# LED_Driver_-_3.net
KiCad netlist of a schematic drawn in Altium Designer
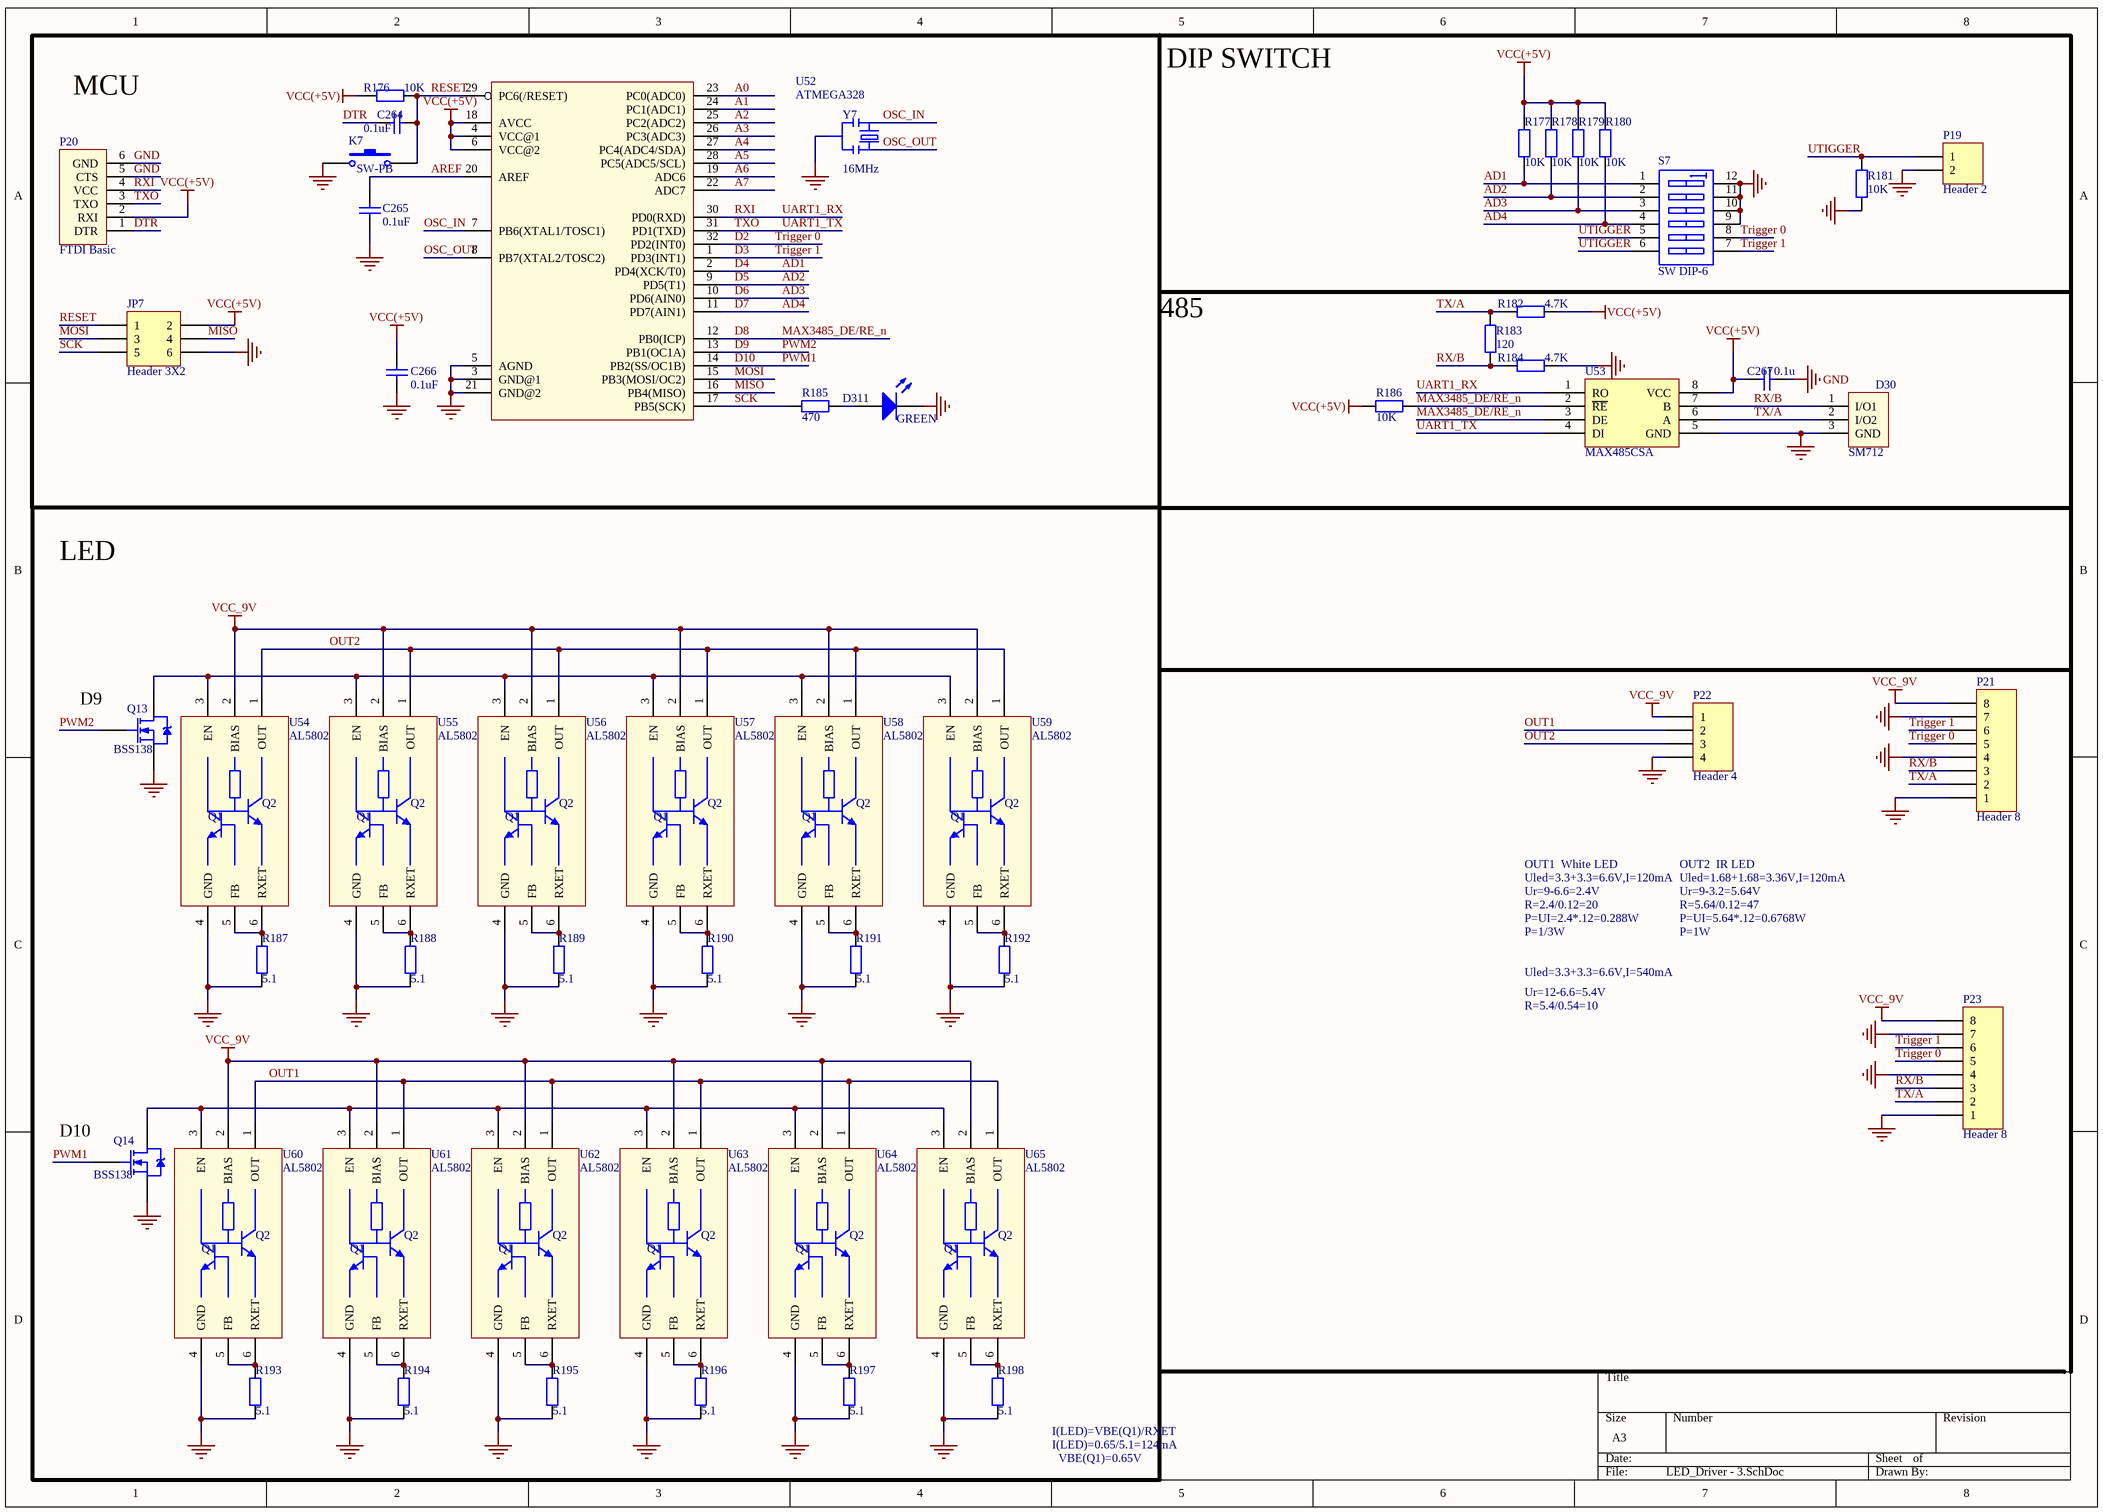
[diagram p0: LED_Driver - 3.SchDoc]

(export (version "E")
  (design (tool "Eeschema 10.0.6"))
  (components
    (comp (ref "C264")
      (value "0.1uF")
      (footprint "C0603")
      (description "Capacitor")
      (fields (field (name "IPARTNUMBER") "C100nF25V10%X7R") (field (name "VOLTAGE") "25V"))
      (libsource (lib "Schlib1") (part "CAP SMT C100nF25V10%X7R"))
    )
    (comp (ref "C265")
      (value "0.1uF")
      (footprint "C0603")
      (description "Capacitor")
      (fields (field (name "IPARTNUMBER") "C100nF25V10%X7R") (field (name "VOLTAGE") "25V"))
      (libsource (lib "Schlib1") (part "CAP SMT C100nF25V10%X7R"))
    )
    (comp (ref "C266")
      (value "0.1uF")
      (footprint "C0603")
      (description "Capacitor")
      (fields (field (name "IPARTNUMBER") "C100nF25V10%X7R") (field (name "VOLTAGE") "25V"))
      (libsource (lib "Schlib1") (part "CAP SMT C100nF25V10%X7R"))
    )
    (comp (ref "C267")
      (value "0.1u")
      (footprint "C0603")
      (description "Capacitor")
      (fields (field (name "PUBLISHER") "Altium Limited"))
      (libsource (lib "Miscellaneous Devices") (part "Cap"))
    )
    (comp (ref "D30")
      (value "SM712")
      (footprint "SOT23-3")
      (libsource (lib "STM32F4_CAM V2.0") (part "SM712"))
    )
    (comp (ref "D31")
      (value "GREEN")
      (footprint "LED0805")
      (description "Typical INFRARED GaAs LED")
      (fields (field (name "PUBLISHER") "Altium Limited"))
      (libsource (lib "DM642") (part "LED0"))
    )
    (comp (ref "JP7")
      (value "Header 3X2")
      (footprint "MHDR1X6")
      (description "Header, 3-Pin, Dual row")
      (fields (field (name "PUBLISHER") "Altium Limited"))
      (libsource (lib "Miscellaneous Connectors") (part "Header 3X2"))
    )
    (comp (ref "K7")
      (value "SW-PB")
      (footprint "157SW")
      (description "Switch")
      (fields (field (name "PUBLISHER") "Altium Limited"))
      (libsource (lib "Miscellaneous Devices") (part "SW-PB"))
    )
    (comp (ref "P19")
      (value "Header 2")
      (footprint "HDR1X2")
      (description "Header, 2-Pin")
      (fields (field (name "PUBLISHER") "Altium Limited"))
      (libsource (lib "Miscellaneous Connectors") (part "Header 2"))
    )
    (comp (ref "P20")
      (value "FTDI Basic")
      (footprint "MHDR1X6")
      (libsource (lib "PCB_Project1") (part "ARDUINO_SERIAL_PROGRAMPTH"))
    )
    (comp (ref "P21")
      (value "Header 8")
      (footprint "SH_1.25MM*8")
      (description "Header, 8-Pin")
      (fields (field (name "PUBLISHER") "Altium Limited"))
      (libsource (lib "Miscellaneous Connectors") (part "Header 8"))
    )
    (comp (ref "P22")
      (value "Header 4")
      (footprint "SMT_1.25MM*4")
      (description "Header, 4-Pin")
      (fields (field (name "PUBLISHER") "Altium Limited"))
      (libsource (lib "Miscellaneous Connectors") (part "Header 4"))
    )
    (comp (ref "P23")
      (value "Header 8")
      (footprint "SH_1.25MM*8")
      (description "Header, 8-Pin")
      (fields (field (name "PUBLISHER") "Altium Limited"))
      (libsource (lib "Miscellaneous Connectors") (part "Header 8"))
    )
    (comp (ref "Q13")
      (value "BSS138")
      (footprint "SOT-23 (Standard)")
      (fields
        (field (name "MANUFACTURER") "Fairchild Semiconductor")
        (field (name "MANUFACTURER PART NUMBER") "BSS123")
      )
      (libsource (lib "Miscellaneous_Devices") (part "NMOS"))
    )
    (comp (ref "Q14")
      (value "BSS138")
      (footprint "SOT-23 (Standard)")
      (fields
        (field (name "MANUFACTURER") "Fairchild Semiconductor")
        (field (name "MANUFACTURER PART NUMBER") "BSS123")
      )
      (libsource (lib "Miscellaneous_Devices") (part "NMOS"))
    )
    (comp (ref "R176")
      (value "10K")
      (footprint "R0603")
      (description "Resistor")
      (libsource (lib "") (part "Res2_1"))
    )
    (comp (ref "R177")
      (value "10K")
      (footprint "R0603")
      (description "Resistor")
      (libsource (lib "DM642") (part "Res2"))
    )
    (comp (ref "R178")
      (value "10K")
      (footprint "R0603")
      (description "Resistor")
      (libsource (lib "DM642") (part "Res2"))
    )
    (comp (ref "R179")
      (value "10K")
      (footprint "R0603")
      (description "Resistor")
      (libsource (lib "DM642") (part "Res2"))
    )
    (comp (ref "R180")
      (value "10K")
      (footprint "R0603")
      (description "Resistor")
      (libsource (lib "DM642") (part "Res2"))
    )
    (comp (ref "R181")
      (value "10K")
      (footprint "R0603")
      (description "Resistor")
      (fields (field (name "PUBLISHER") "Altium Limited"))
      (libsource (lib "Miscellaneous Devices") (part "Res2"))
    )
    (comp (ref "R182")
      (value "4.7K")
      (footprint "R0603")
      (description "Resistor")
      (libsource (lib "") (part "Res2_2"))
    )
    (comp (ref "R183")
      (value "120")
      (footprint "R0603")
      (description "Resistor")
      (libsource (lib "DM642") (part "Res2"))
    )
    (comp (ref "R184")
      (value "4.7K")
      (footprint "R0603")
      (description "Resistor")
      (libsource (lib "") (part "Res2_2"))
    )
    (comp (ref "R185")
      (value "470")
      (footprint "R0603")
      (description "Resistor")
      (libsource (lib "") (part "Res2_1"))
    )
    (comp (ref "R186")
      (value "10K")
      (footprint "R0603")
      (description "Resistor")
      (libsource (lib "") (part "Res2_2"))
    )
    (comp (ref "R187")
      (value "5.1")
      (footprint "R0603")
      (description "Resistor")
      (libsource (lib "DM642") (part "Res2"))
    )
    (comp (ref "R188")
      (value "5.1")
      (footprint "R0603")
      (description "Resistor")
      (libsource (lib "DM642") (part "Res2"))
    )
    (comp (ref "R189")
      (value "5.1")
      (footprint "R0603")
      (description "Resistor")
      (libsource (lib "DM642") (part "Res2"))
    )
    (comp (ref "R190")
      (value "5.1")
      (footprint "R0603")
      (description "Resistor")
      (libsource (lib "DM642") (part "Res2"))
    )
    (comp (ref "R191")
      (value "5.1")
      (footprint "R0603")
      (description "Resistor")
      (libsource (lib "DM642") (part "Res2"))
    )
    (comp (ref "R192")
      (value "5.1")
      (footprint "R0603")
      (description "Resistor")
      (libsource (lib "DM642") (part "Res2"))
    )
    (comp (ref "R193")
      (value "5.1")
      (footprint "R0603")
      (description "Resistor")
      (libsource (lib "DM642") (part "Res2"))
    )
    (comp (ref "R194")
      (value "5.1")
      (footprint "R0603")
      (description "Resistor")
      (libsource (lib "DM642") (part "Res2"))
    )
    (comp (ref "R195")
      (value "5.1")
      (footprint "R0603")
      (description "Resistor")
      (libsource (lib "DM642") (part "Res2"))
    )
    (comp (ref "R196")
      (value "5.1")
      (footprint "R0603")
      (description "Resistor")
      (libsource (lib "DM642") (part "Res2"))
    )
    (comp (ref "R197")
      (value "5.1")
      (footprint "R0603")
      (description "Resistor")
      (libsource (lib "DM642") (part "Res2"))
    )
    (comp (ref "R198")
      (value "5.1")
      (footprint "R0603")
      (description "Resistor")
      (libsource (lib "DM642") (part "Res2"))
    )
    (comp (ref "S7")
      (value "SW DIP-6")
      (footprint "DIP_SW_6WAY_SMD")
      (description "DIP Switch, 6 Position, SPST")
      (fields (field (name "PUBLISHER") "Altium Limited"))
      (libsource (lib "Miscellaneous Devices") (part "SW DIP-6"))
    )
    (comp (ref "U52")
      (value "ATMEGA328")
      (footprint "TQFP32-08")
      (libsource (lib "PCB_Project1") (part "ATMEGA168"))
    )
    (comp (ref "U53")
      (value "MAX485CSA")
      (footprint "SOIC-8")
      (libsource (lib "STM32F4_CAM V1.2") (part "MAX3485CSA"))
    )
    (comp (ref "U54") (value "AL5802") (footprint "SOT26") (libsource (lib "LED") (part "AL5802")))
    (comp (ref "U55") (value "AL5802") (footprint "SOT26") (libsource (lib "LED") (part "AL5802")))
    (comp (ref "U56") (value "AL5802") (footprint "SOT26") (libsource (lib "LED") (part "AL5802")))
    (comp (ref "U57") (value "AL5802") (footprint "SOT26") (libsource (lib "LED") (part "AL5802")))
    (comp (ref "U58") (value "AL5802") (footprint "SOT26") (libsource (lib "LED") (part "AL5802")))
    (comp (ref "U59") (value "AL5802") (footprint "SOT26") (libsource (lib "LED") (part "AL5802")))
    (comp (ref "U60") (value "AL5802") (footprint "SOT26") (libsource (lib "LED") (part "AL5802")))
    (comp (ref "U61") (value "AL5802") (footprint "SOT26") (libsource (lib "LED") (part "AL5802")))
    (comp (ref "U62") (value "AL5802") (footprint "SOT26") (libsource (lib "LED") (part "AL5802")))
    (comp (ref "U63") (value "AL5802") (footprint "SOT26") (libsource (lib "LED") (part "AL5802")))
    (comp (ref "U64") (value "AL5802") (footprint "SOT26") (libsource (lib "LED") (part "AL5802")))
    (comp (ref "U65") (value "AL5802") (footprint "SOT26") (libsource (lib "LED") (part "AL5802")))
    (comp (ref "Y7")
      (value "16MHz")
      (footprint "RESONATOR-SMD")
      (libsource (lib "SparkFun") (part "RESONATORSMD"))
    )
  )
  (nets
    (net (code "1") (name "/A0") (class "Default")
      (node (ref "U52") (pin "23") (pinfunction "PC0(ADC0)_23") (pintype "passive"))
    )
    (net (code "2") (name "/A1") (class "Default")
      (node (ref "U52") (pin "24") (pinfunction "PC1(ADC1)_24") (pintype "passive"))
    )
    (net (code "3") (name "/A2") (class "Default")
      (node (ref "U52") (pin "25") (pinfunction "PC2(ADC2)_25") (pintype "passive"))
    )
    (net (code "4") (name "/A3") (class "Default")
      (node (ref "U52") (pin "26") (pinfunction "PC3(ADC3)_26") (pintype "passive"))
    )
    (net (code "5") (name "/A4") (class "Default")
      (node (ref "U52") (pin "27") (pinfunction "PC4(ADC4/SDA)_27") (pintype "passive"))
    )
    (net (code "6") (name "/A5") (class "Default")
      (node (ref "U52") (pin "28") (pinfunction "PC5(ADC5/SCL)_28") (pintype "passive"))
    )
    (net (code "7") (name "/A6") (class "Default")
      (node (ref "U52") (pin "19") (pinfunction "ADC6_19") (pintype "passive"))
    )
    (net (code "8") (name "/A7") (class "Default")
      (node (ref "U52") (pin "22") (pinfunction "ADC7_22") (pintype "passive"))
    )
    (net (code "9") (name "/AD1") (class "Default")
      (node (ref "R177") (pin "2") (pinfunction "2_2") (pintype "passive"))
      (node (ref "S7") (pin "1") (pinfunction "A1_1") (pintype "passive"))
      (node (ref "U52") (pin "2") (pinfunction "PD4(XCK/T0)_2") (pintype "passive"))
    )
    (net (code "10") (name "/AD2") (class "Default")
      (node (ref "R178") (pin "2") (pinfunction "2_2") (pintype "passive"))
      (node (ref "S7") (pin "2") (pinfunction "A2_2") (pintype "passive"))
      (node (ref "U52") (pin "9") (pinfunction "PD5(T1)_9") (pintype "passive"))
    )
    (net (code "11") (name "/AD3") (class "Default")
      (node (ref "R179") (pin "2") (pinfunction "2_2") (pintype "passive"))
      (node (ref "S7") (pin "3") (pinfunction "A3_3") (pintype "passive"))
      (node (ref "U52") (pin "10") (pinfunction "PD6(AIN0)_10") (pintype "passive"))
    )
    (net (code "12") (name "/AD4") (class "Default")
      (node (ref "R180") (pin "2") (pinfunction "2_2") (pintype "passive"))
      (node (ref "S7") (pin "4") (pinfunction "A4_4") (pintype "passive"))
      (node (ref "U52") (pin "11") (pinfunction "PD7(AIN1)_11") (pintype "passive"))
    )
    (net (code "13") (name "/AREF") (class "Default")
      (node (ref "C265") (pin "2") (pinfunction "2_2") (pintype "passive"))
      (node (ref "U52") (pin "20") (pinfunction "AREF_20") (pintype "passive"))
    )
    (net (code "14") (name "/D2") (class "Default")
      (node (ref "P21") (pin "5") (pinfunction "5_5") (pintype "passive"))
      (node (ref "P23") (pin "5") (pinfunction "5_5") (pintype "passive"))
      (node (ref "S7") (pin "8") (pinfunction "B5_8") (pintype "passive"))
      (node (ref "U52") (pin "32") (pinfunction "PD2(INT0)_32") (pintype "passive"))
    )
    (net (code "15") (name "/D3") (class "Default")
      (node (ref "P21") (pin "6") (pinfunction "6_6") (pintype "passive"))
      (node (ref "P23") (pin "6") (pinfunction "6_6") (pintype "passive"))
      (node (ref "S7") (pin "7") (pinfunction "B6_7") (pintype "passive"))
      (node (ref "U52") (pin "1") (pinfunction "PD3(INT1)_1") (pintype "passive"))
    )
    (net (code "16") (name "/D8") (class "Default")
      (node (ref "R186") (pin "1") (pinfunction "1_1") (pintype "passive"))
      (node (ref "U52") (pin "12") (pinfunction "PB0(ICP)_12") (pintype "passive"))
      (node (ref "U53") (pin "2") (pinfunction "~{RE}_2") (pintype "passive"))
      (node (ref "U53") (pin "3") (pinfunction "DE_3") (pintype "passive"))
    )
    (net (code "17") (name "/D9") (class "Default")
      (node (ref "Q13") (pin "G") (pinfunction "G_G") (pintype "passive"))
      (node (ref "U52") (pin "13") (pinfunction "PB1(OC1A)_13") (pintype "passive"))
    )
    (net (code "18") (name "/D10") (class "Default")
      (node (ref "Q14") (pin "G") (pinfunction "G_G") (pintype "passive"))
      (node (ref "U52") (pin "14") (pinfunction "PB2(SS/OC1B)_14") (pintype "passive"))
    )
    (net (code "19") (name "/DTR") (class "Default")
      (node (ref "C264") (pin "1") (pinfunction "1_1") (pintype "passive"))
      (node (ref "P20") (pin "1") (pinfunction "DTR_1") (pintype "passive"))
    )
    (net (code "20") (name "/MISO") (class "Default")
      (node (ref "JP7") (pin "4") (pinfunction "4_4") (pintype "passive"))
      (node (ref "U52") (pin "16") (pinfunction "PB4(MISO)_16") (pintype "passive"))
    )
    (net (code "21") (name "/MOSI") (class "Default")
      (node (ref "JP7") (pin "3") (pinfunction "3_3") (pintype "passive"))
      (node (ref "U52") (pin "15") (pinfunction "PB3(MOSI/OC2)_15") (pintype "passive"))
    )
    (net (code "22") (name "/OSC_IN") (class "Default")
      (node (ref "U52") (pin "7") (pinfunction "PB6(XTAL1/TOSC1)_7") (pintype "passive"))
      (node (ref "Y7") (pin "3") (pinfunction "3_3") (pintype "passive"))
    )
    (net (code "23") (name "/OSC_OUT") (class "Default")
      (node (ref "U52") (pin "8") (pinfunction "PB7(XTAL2/TOSC2)_8") (pintype "passive"))
      (node (ref "Y7") (pin "1") (pinfunction "1_1") (pintype "passive"))
    )
    (net (code "24") (name "/OUT1") (class "Default")
      (node (ref "P22") (pin "2") (pinfunction "2_2") (pintype "passive"))
      (node (ref "U60") (pin "1") (pinfunction "OUT_1") (pintype "passive"))
      (node (ref "U61") (pin "1") (pinfunction "OUT_1") (pintype "passive"))
      (node (ref "U62") (pin "1") (pinfunction "OUT_1") (pintype "passive"))
      (node (ref "U63") (pin "1") (pinfunction "OUT_1") (pintype "passive"))
      (node (ref "U64") (pin "1") (pinfunction "OUT_1") (pintype "passive"))
      (node (ref "U65") (pin "1") (pinfunction "OUT_1") (pintype "passive"))
    )
    (net (code "25") (name "/OUT2") (class "Default")
      (node (ref "P22") (pin "3") (pinfunction "3_3") (pintype "passive"))
      (node (ref "U54") (pin "1") (pinfunction "OUT_1") (pintype "passive"))
      (node (ref "U55") (pin "1") (pinfunction "OUT_1") (pintype "passive"))
      (node (ref "U56") (pin "1") (pinfunction "OUT_1") (pintype "passive"))
      (node (ref "U57") (pin "1") (pinfunction "OUT_1") (pintype "passive"))
      (node (ref "U58") (pin "1") (pinfunction "OUT_1") (pintype "passive"))
      (node (ref "U59") (pin "1") (pinfunction "OUT_1") (pintype "passive"))
    )
    (net (code "26") (name "/RESET") (class "Default")
      (node (ref "C264") (pin "2") (pinfunction "2_2") (pintype "passive"))
      (node (ref "JP7") (pin "1") (pinfunction "1_1") (pintype "passive"))
      (node (ref "K7") (pin "2") (pinfunction "2_2") (pintype "passive"))
      (node (ref "R176") (pin "2") (pinfunction "2_2") (pintype "passive"))
      (node (ref "U52") (pin "29") (pinfunction "PC6(/RESET)_29") (pintype "passive"))
    )
    (net (code "27") (name "/RXI") (class "Default")
      (node (ref "P20") (pin "4") (pinfunction "VCC_4") (pintype "passive"))
      (node (ref "U52") (pin "30") (pinfunction "PD0(RXD)_30") (pintype "passive"))
      (node (ref "U53") (pin "1") (pinfunction "RO_1") (pintype "passive"))
    )
    (net (code "28") (name "/RX{slash}B") (class "Default")
      (node (ref "D30") (pin "1") (pinfunction "I/O1_1") (pintype "passive"))
      (node (ref "P21") (pin "3") (pinfunction "3_3") (pintype "passive"))
      (node (ref "P23") (pin "3") (pinfunction "3_3") (pintype "passive"))
      (node (ref "R183") (pin "2") (pinfunction "2_2") (pintype "passive"))
      (node (ref "R184") (pin "2") (pinfunction "2_2") (pintype "passive"))
      (node (ref "U53") (pin "7") (pinfunction "B_7") (pintype "passive"))
    )
    (net (code "29") (name "/SCK") (class "Default")
      (node (ref "JP7") (pin "5") (pinfunction "5_5") (pintype "passive"))
      (node (ref "R185") (pin "1") (pinfunction "1_1") (pintype "passive"))
      (node (ref "U52") (pin "17") (pinfunction "PB5(SCK)_17") (pintype "passive"))
    )
    (net (code "30") (name "/TXO") (class "Default")
      (node (ref "P20") (pin "3") (pinfunction "TXO_3") (pintype "passive"))
      (node (ref "U52") (pin "31") (pinfunction "PD1(TXD)_31") (pintype "passive"))
      (node (ref "U53") (pin "4") (pinfunction "DI_4") (pintype "passive"))
    )
    (net (code "31") (name "/TX{slash}A") (class "Default")
      (node (ref "D30") (pin "2") (pinfunction "I/O2_2") (pintype "passive"))
      (node (ref "P21") (pin "2") (pinfunction "2_2") (pintype "passive"))
      (node (ref "P23") (pin "2") (pinfunction "2_2") (pintype "passive"))
      (node (ref "R182") (pin "2") (pinfunction "2_2") (pintype "passive"))
      (node (ref "R183") (pin "1") (pinfunction "1_1") (pintype "passive"))
      (node (ref "U53") (pin "6") (pinfunction "A_6") (pintype "passive"))
    )
    (net (code "32") (name "/UTIGGER") (class "Default")
      (node (ref "P19") (pin "1") (pinfunction "1_1") (pintype "passive"))
      (node (ref "R181") (pin "2") (pinfunction "2_2") (pintype "passive"))
      (node (ref "S7") (pin "5") (pinfunction "A5_5") (pintype "passive"))
      (node (ref "S7") (pin "6") (pinfunction "A6_6") (pintype "passive"))
    )
    (net (code "33") (name "GND") (class "Default")
      (node (ref "C265") (pin "1") (pinfunction "1_1") (pintype "passive"))
      (node (ref "C266") (pin "2") (pinfunction "2_2") (pintype "passive"))
      (node (ref "C267") (pin "1") (pinfunction "1_1") (pintype "passive"))
      (node (ref "D30") (pin "3") (pinfunction "GND_3") (pintype "passive"))
      (node (ref "D31") (pin "2") (pinfunction "K_2") (pintype "passive"))
      (node (ref "JP7") (pin "6") (pinfunction "6_6") (pintype "passive"))
      (node (ref "K7") (pin "1") (pinfunction "1_1") (pintype "passive"))
      (node (ref "P19") (pin "2") (pinfunction "2_2") (pintype "passive"))
      (node (ref "P20") (pin "5") (pinfunction "CTS_5") (pintype "passive"))
      (node (ref "P20") (pin "6") (pinfunction "GND_6") (pintype "passive"))
      (node (ref "P21") (pin "1") (pinfunction "1_1") (pintype "passive"))
      (node (ref "P21") (pin "4") (pinfunction "4_4") (pintype "passive"))
      (node (ref "P21") (pin "7") (pinfunction "7_7") (pintype "passive"))
      (node (ref "P22") (pin "4") (pinfunction "4_4") (pintype "passive"))
      (node (ref "P23") (pin "1") (pinfunction "1_1") (pintype "passive"))
      (node (ref "P23") (pin "4") (pinfunction "4_4") (pintype "passive"))
      (node (ref "P23") (pin "7") (pinfunction "7_7") (pintype "passive"))
      (node (ref "Q13") (pin "S") (pinfunction "S_S") (pintype "passive"))
      (node (ref "Q14") (pin "S") (pinfunction "S_S") (pintype "passive"))
      (node (ref "R181") (pin "1") (pinfunction "1_1") (pintype "passive"))
      (node (ref "R184") (pin "1") (pinfunction "1_1") (pintype "passive"))
      (node (ref "R187") (pin "2") (pinfunction "2_2") (pintype "passive"))
      (node (ref "R188") (pin "2") (pinfunction "2_2") (pintype "passive"))
      (node (ref "R189") (pin "2") (pinfunction "2_2") (pintype "passive"))
      (node (ref "R190") (pin "2") (pinfunction "2_2") (pintype "passive"))
      (node (ref "R191") (pin "2") (pinfunction "2_2") (pintype "passive"))
      (node (ref "R192") (pin "2") (pinfunction "2_2") (pintype "passive"))
      (node (ref "R193") (pin "2") (pinfunction "2_2") (pintype "passive"))
      (node (ref "R194") (pin "2") (pinfunction "2_2") (pintype "passive"))
      (node (ref "R195") (pin "2") (pinfunction "2_2") (pintype "passive"))
      (node (ref "R196") (pin "2") (pinfunction "2_2") (pintype "passive"))
      (node (ref "R197") (pin "2") (pinfunction "2_2") (pintype "passive"))
      (node (ref "R198") (pin "2") (pinfunction "2_2") (pintype "passive"))
      (node (ref "S7") (pin "10") (pinfunction "B3_10") (pintype "passive"))
      (node (ref "S7") (pin "11") (pinfunction "B2_11") (pintype "passive"))
      (node (ref "S7") (pin "12") (pinfunction "B1_12") (pintype "passive"))
      (node (ref "S7") (pin "9") (pinfunction "B4_9") (pintype "passive"))
      (node (ref "U52") (pin "21") (pinfunction "GND@2_21") (pintype "passive"))
      (node (ref "U52") (pin "3") (pinfunction "GND@1_3") (pintype "passive"))
      (node (ref "U52") (pin "5") (pinfunction "AGND_5") (pintype "passive"))
      (node (ref "U53") (pin "5") (pinfunction "GND_5") (pintype "passive"))
      (node (ref "U54") (pin "4") (pinfunction "GND_4") (pintype "passive"))
      (node (ref "U55") (pin "4") (pinfunction "GND_4") (pintype "passive"))
      (node (ref "U56") (pin "4") (pinfunction "GND_4") (pintype "passive"))
      (node (ref "U57") (pin "4") (pinfunction "GND_4") (pintype "passive"))
      (node (ref "U58") (pin "4") (pinfunction "GND_4") (pintype "passive"))
      (node (ref "U59") (pin "4") (pinfunction "GND_4") (pintype "passive"))
      (node (ref "U60") (pin "4") (pinfunction "GND_4") (pintype "passive"))
      (node (ref "U61") (pin "4") (pinfunction "GND_4") (pintype "passive"))
      (node (ref "U62") (pin "4") (pinfunction "GND_4") (pintype "passive"))
      (node (ref "U63") (pin "4") (pinfunction "GND_4") (pintype "passive"))
      (node (ref "U64") (pin "4") (pinfunction "GND_4") (pintype "passive"))
      (node (ref "U65") (pin "4") (pinfunction "GND_4") (pintype "passive"))
      (node (ref "Y7") (pin "2") (pinfunction "2_2") (pintype "passive"))
    )
    (net (code "34") (name "Net-(D31-A)") (class "Default")
      (node (ref "D31") (pin "1") (pinfunction "A_1") (pintype "passive"))
      (node (ref "R185") (pin "2") (pinfunction "2_2") (pintype "passive"))
    )
    (net (code "35") (name "Net-(U54-EN)") (class "Default")
      (node (ref "Q13") (pin "D") (pinfunction "D_D") (pintype "passive"))
      (node (ref "U54") (pin "3") (pinfunction "EN_3") (pintype "passive"))
      (node (ref "U55") (pin "3") (pinfunction "EN_3") (pintype "passive"))
      (node (ref "U56") (pin "3") (pinfunction "EN_3") (pintype "passive"))
      (node (ref "U57") (pin "3") (pinfunction "EN_3") (pintype "passive"))
      (node (ref "U58") (pin "3") (pinfunction "EN_3") (pintype "passive"))
      (node (ref "U59") (pin "3") (pinfunction "EN_3") (pintype "passive"))
    )
    (net (code "36") (name "Net-(U54-FB)") (class "Default")
      (node (ref "R187") (pin "1") (pinfunction "1_1") (pintype "passive"))
      (node (ref "U54") (pin "5") (pinfunction "FB_5") (pintype "passive"))
      (node (ref "U54") (pin "6") (pinfunction "RXET_6") (pintype "passive"))
    )
    (net (code "37") (name "Net-(U55-FB)") (class "Default")
      (node (ref "R188") (pin "1") (pinfunction "1_1") (pintype "passive"))
      (node (ref "U55") (pin "5") (pinfunction "FB_5") (pintype "passive"))
      (node (ref "U55") (pin "6") (pinfunction "RXET_6") (pintype "passive"))
    )
    (net (code "38") (name "Net-(U56-FB)") (class "Default")
      (node (ref "R189") (pin "1") (pinfunction "1_1") (pintype "passive"))
      (node (ref "U56") (pin "5") (pinfunction "FB_5") (pintype "passive"))
      (node (ref "U56") (pin "6") (pinfunction "RXET_6") (pintype "passive"))
    )
    (net (code "39") (name "Net-(U57-FB)") (class "Default")
      (node (ref "R190") (pin "1") (pinfunction "1_1") (pintype "passive"))
      (node (ref "U57") (pin "5") (pinfunction "FB_5") (pintype "passive"))
      (node (ref "U57") (pin "6") (pinfunction "RXET_6") (pintype "passive"))
    )
    (net (code "40") (name "Net-(U58-FB)") (class "Default")
      (node (ref "R191") (pin "1") (pinfunction "1_1") (pintype "passive"))
      (node (ref "U58") (pin "5") (pinfunction "FB_5") (pintype "passive"))
      (node (ref "U58") (pin "6") (pinfunction "RXET_6") (pintype "passive"))
    )
    (net (code "41") (name "Net-(U59-FB)") (class "Default")
      (node (ref "R192") (pin "1") (pinfunction "1_1") (pintype "passive"))
      (node (ref "U59") (pin "5") (pinfunction "FB_5") (pintype "passive"))
      (node (ref "U59") (pin "6") (pinfunction "RXET_6") (pintype "passive"))
    )
    (net (code "42") (name "Net-(U60-EN)") (class "Default")
      (node (ref "Q14") (pin "D") (pinfunction "D_D") (pintype "passive"))
      (node (ref "U60") (pin "3") (pinfunction "EN_3") (pintype "passive"))
      (node (ref "U61") (pin "3") (pinfunction "EN_3") (pintype "passive"))
      (node (ref "U62") (pin "3") (pinfunction "EN_3") (pintype "passive"))
      (node (ref "U63") (pin "3") (pinfunction "EN_3") (pintype "passive"))
      (node (ref "U64") (pin "3") (pinfunction "EN_3") (pintype "passive"))
      (node (ref "U65") (pin "3") (pinfunction "EN_3") (pintype "passive"))
    )
    (net (code "43") (name "Net-(U60-FB)") (class "Default")
      (node (ref "R193") (pin "1") (pinfunction "1_1") (pintype "passive"))
      (node (ref "U60") (pin "5") (pinfunction "FB_5") (pintype "passive"))
      (node (ref "U60") (pin "6") (pinfunction "RXET_6") (pintype "passive"))
    )
    (net (code "44") (name "Net-(U61-FB)") (class "Default")
      (node (ref "R194") (pin "1") (pinfunction "1_1") (pintype "passive"))
      (node (ref "U61") (pin "5") (pinfunction "FB_5") (pintype "passive"))
      (node (ref "U61") (pin "6") (pinfunction "RXET_6") (pintype "passive"))
    )
    (net (code "45") (name "Net-(U62-FB)") (class "Default")
      (node (ref "R195") (pin "1") (pinfunction "1_1") (pintype "passive"))
      (node (ref "U62") (pin "5") (pinfunction "FB_5") (pintype "passive"))
      (node (ref "U62") (pin "6") (pinfunction "RXET_6") (pintype "passive"))
    )
    (net (code "46") (name "Net-(U63-FB)") (class "Default")
      (node (ref "R196") (pin "1") (pinfunction "1_1") (pintype "passive"))
      (node (ref "U63") (pin "5") (pinfunction "FB_5") (pintype "passive"))
      (node (ref "U63") (pin "6") (pinfunction "RXET_6") (pintype "passive"))
    )
    (net (code "47") (name "Net-(U64-FB)") (class "Default")
      (node (ref "R197") (pin "1") (pinfunction "1_1") (pintype "passive"))
      (node (ref "U64") (pin "5") (pinfunction "FB_5") (pintype "passive"))
      (node (ref "U64") (pin "6") (pinfunction "RXET_6") (pintype "passive"))
    )
    (net (code "48") (name "Net-(U65-FB)") (class "Default")
      (node (ref "R198") (pin "1") (pinfunction "1_1") (pintype "passive"))
      (node (ref "U65") (pin "5") (pinfunction "FB_5") (pintype "passive"))
      (node (ref "U65") (pin "6") (pinfunction "RXET_6") (pintype "passive"))
    )
    (net (code "49") (name "VCC(+5V)") (class "Default")
      (node (ref "C266") (pin "1") (pinfunction "1_1") (pintype "passive"))
      (node (ref "C267") (pin "2") (pinfunction "2_2") (pintype "passive"))
      (node (ref "JP7") (pin "2") (pinfunction "2_2") (pintype "passive"))
      (node (ref "P20") (pin "2") (pinfunction "RXI_2") (pintype "passive"))
      (node (ref "R176") (pin "1") (pinfunction "1_1") (pintype "passive"))
      (node (ref "R177") (pin "1") (pinfunction "1_1") (pintype "passive"))
      (node (ref "R178") (pin "1") (pinfunction "1_1") (pintype "passive"))
      (node (ref "R179") (pin "1") (pinfunction "1_1") (pintype "passive"))
      (node (ref "R180") (pin "1") (pinfunction "1_1") (pintype "passive"))
      (node (ref "R182") (pin "1") (pinfunction "1_1") (pintype "passive"))
      (node (ref "R186") (pin "2") (pinfunction "2_2") (pintype "passive"))
      (node (ref "U52") (pin "18") (pinfunction "AVCC_18") (pintype "passive"))
      (node (ref "U52") (pin "4") (pinfunction "VCC@1_4") (pintype "passive"))
      (node (ref "U52") (pin "6") (pinfunction "VCC@2_6") (pintype "passive"))
      (node (ref "U53") (pin "8") (pinfunction "VCC_8") (pintype "passive"))
    )
    (net (code "50") (name "VCC_9V") (class "Default")
      (node (ref "P21") (pin "8") (pinfunction "8_8") (pintype "passive"))
      (node (ref "P22") (pin "1") (pinfunction "1_1") (pintype "passive"))
      (node (ref "P23") (pin "8") (pinfunction "8_8") (pintype "passive"))
      (node (ref "U54") (pin "2") (pinfunction "BIAS_2") (pintype "passive"))
      (node (ref "U55") (pin "2") (pinfunction "BIAS_2") (pintype "passive"))
      (node (ref "U56") (pin "2") (pinfunction "BIAS_2") (pintype "passive"))
      (node (ref "U57") (pin "2") (pinfunction "BIAS_2") (pintype "passive"))
      (node (ref "U58") (pin "2") (pinfunction "BIAS_2") (pintype "passive"))
      (node (ref "U59") (pin "2") (pinfunction "BIAS_2") (pintype "passive"))
      (node (ref "U60") (pin "2") (pinfunction "BIAS_2") (pintype "passive"))
      (node (ref "U61") (pin "2") (pinfunction "BIAS_2") (pintype "passive"))
      (node (ref "U62") (pin "2") (pinfunction "BIAS_2") (pintype "passive"))
      (node (ref "U63") (pin "2") (pinfunction "BIAS_2") (pintype "passive"))
      (node (ref "U64") (pin "2") (pinfunction "BIAS_2") (pintype "passive"))
      (node (ref "U65") (pin "2") (pinfunction "BIAS_2") (pintype "passive"))
    )
  )
)
